# signal_inverter.net
KiCad netlist of a schematic drawn in EAGLE
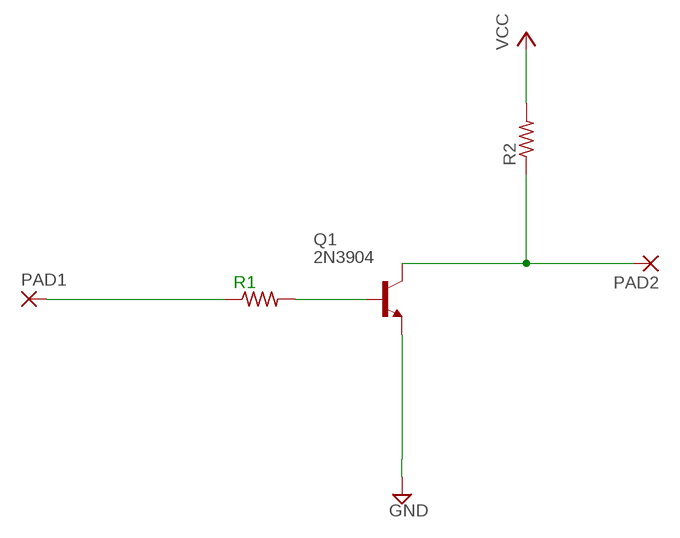
[diagram p0: schematic, sheet 1]

(export (version "E")
  (design (tool "Eeschema 10.0.6"))
  (components
    (comp (ref "PAD1")
      (value "2,15/1,0")
      (footprint "eagle-import:2,15_1,0")
      (libsource (lib "eagle-import") (part "2,15/1,0"))
    )
    (comp (ref "PAD2")
      (value "2,15/1,0")
      (footprint "eagle-import:2,15_1,0")
      (libsource (lib "eagle-import") (part "2,15/1,0"))
    )
    (comp (ref "Q1")
      (value "2N3904")
      (footprint "eagle-import:TO92")
      (libsource (lib "eagle-import") (part "2N3904"))
    )
    (comp (ref "R1")
      (value "R-US_0204/7")
      (footprint "eagle-import:0204_7")
      (libsource (lib "eagle-import") (part "R-US_0204/7"))
    )
    (comp (ref "R2")
      (value "R-US_0204/7")
      (footprint "eagle-import:0204_7")
      (libsource (lib "eagle-import") (part "R-US_0204/7"))
    )
  )
  (nets
    (net (code "1") (name "GND") (class "Default")
      (node (ref "Q1") (pin "3") (pinfunction "E_3") (pintype "passive"))
    )
    (net (code "2") (name "Net-(PAD1-P)") (class "Default")
      (node (ref "PAD1") (pin "1") (pinfunction "P_1") (pintype "passive"))
      (node (ref "R1") (pin "1") (pinfunction "1_1") (pintype "passive"))
    )
    (net (code "3") (name "Net-(PAD2-P)") (class "Default")
      (node (ref "PAD2") (pin "1") (pinfunction "P_1") (pintype "passive"))
      (node (ref "Q1") (pin "1") (pinfunction "C_1") (pintype "passive"))
      (node (ref "R2") (pin "1") (pinfunction "1_1") (pintype "passive"))
    )
    (net (code "4") (name "Net-(Q1-B)") (class "Default")
      (node (ref "Q1") (pin "2") (pinfunction "B_2") (pintype "passive"))
      (node (ref "R1") (pin "2") (pinfunction "2_2") (pintype "passive"))
    )
    (net (code "5") (name "VCC") (class "Default")
      (node (ref "R2") (pin "2") (pinfunction "2_2") (pintype "passive"))
    )
  )
)
